# WaterMonitorV7_0.net
KiCad netlist of a schematic drawn in EAGLE
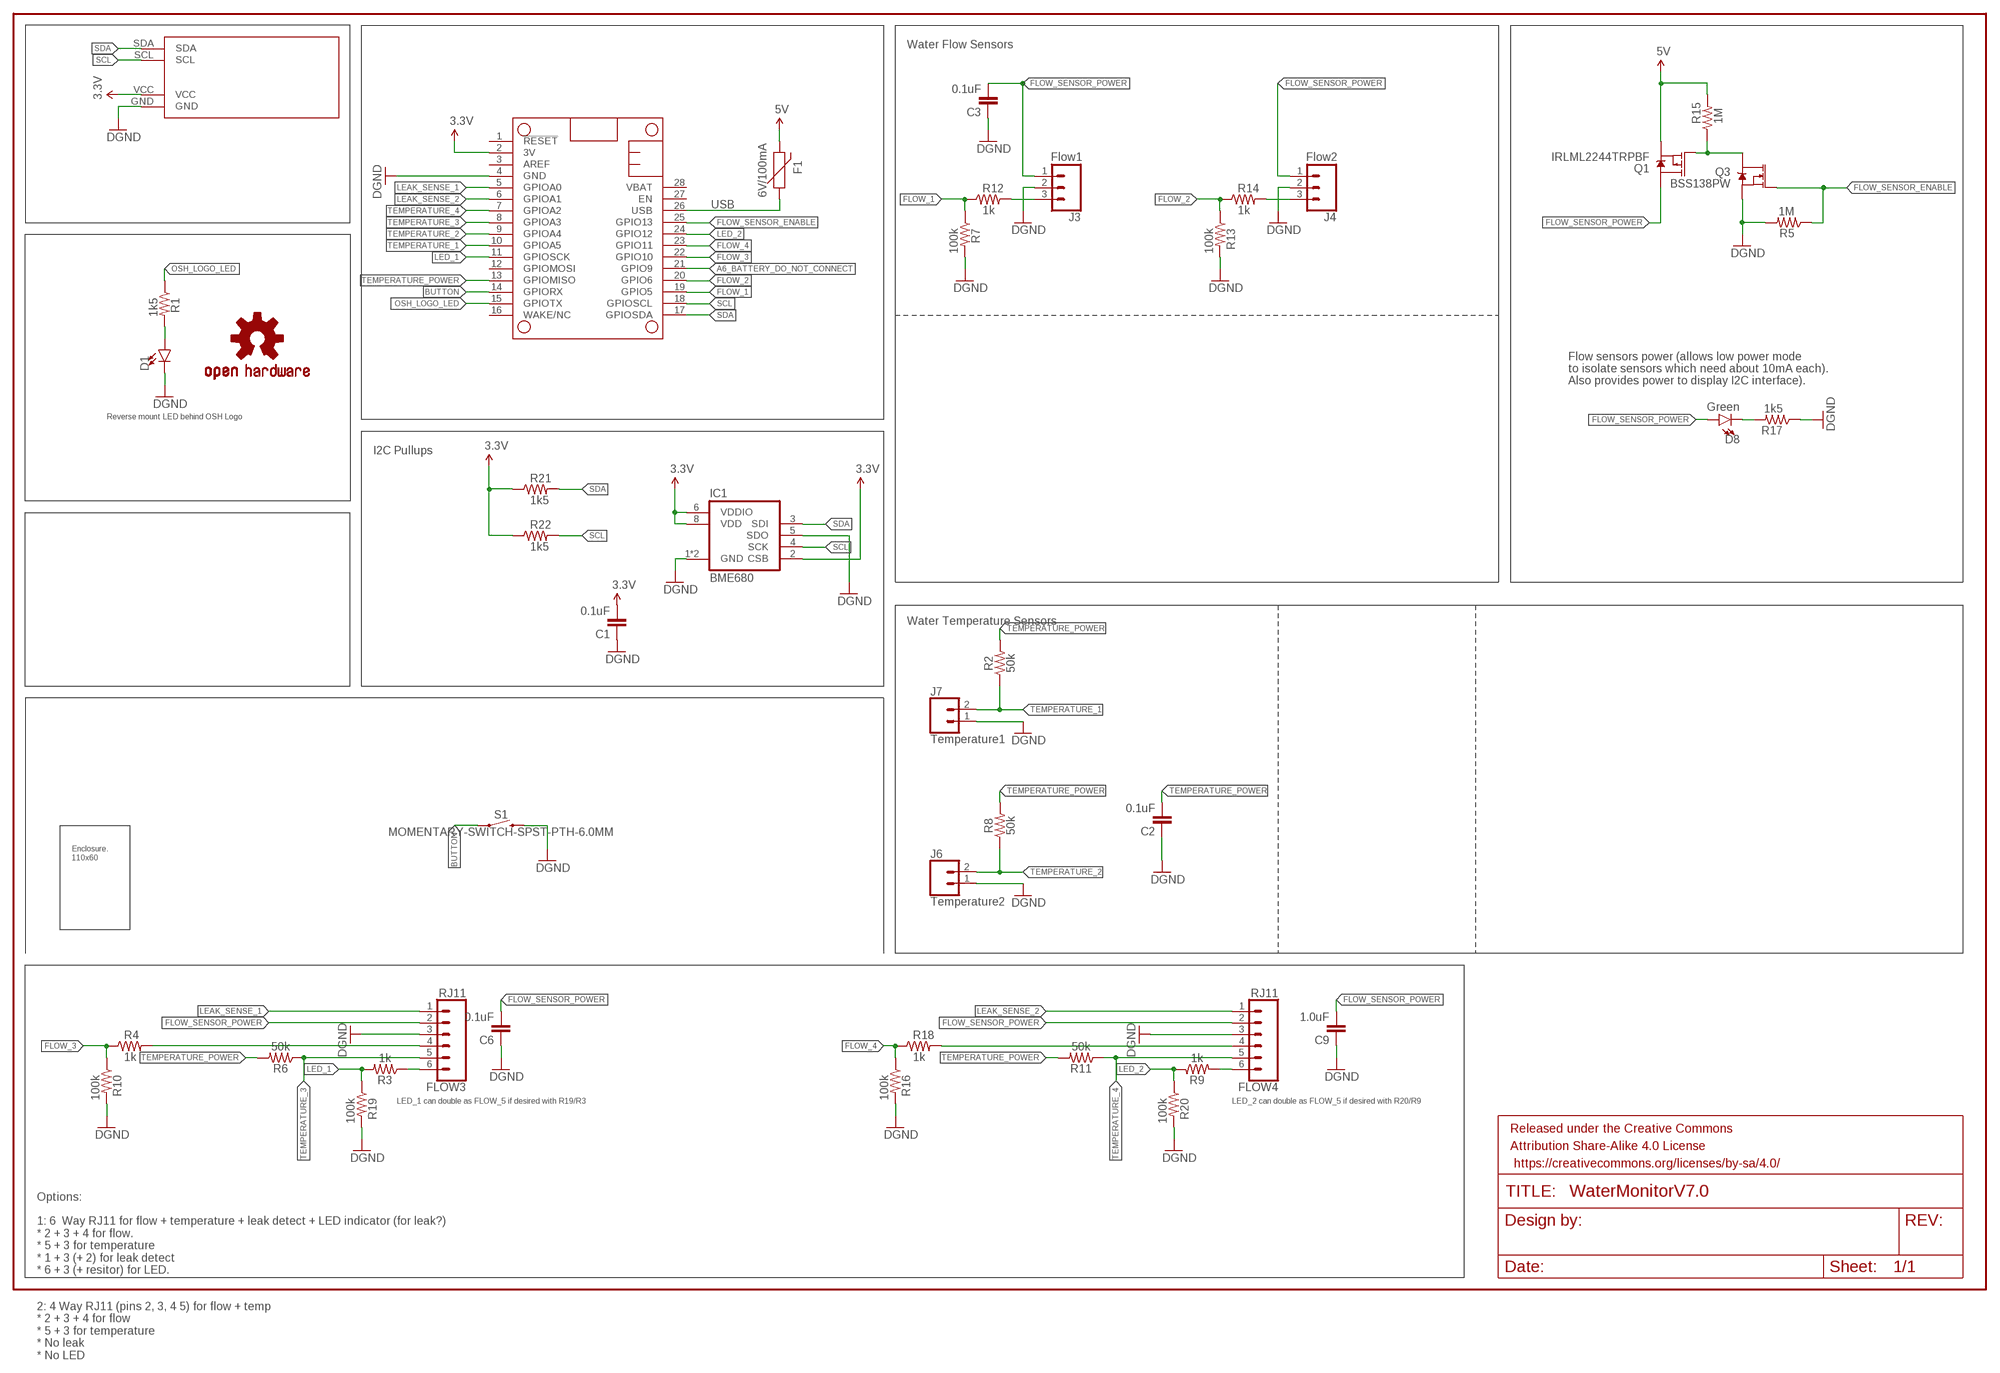
[diagram p0: schematic, sheet 1]

(export (version "E")
  (design (tool "Eeschema 10.0.6"))
  (components
    (comp (ref "C1")
      (value "0.1uF")
      (footprint "eagle-import:0805")
      (libsource (lib "eagle-import") (part "CAP0805"))
    )
    (comp (ref "C2")
      (value "0.1uF")
      (footprint "eagle-import:0805")
      (libsource (lib "eagle-import") (part "CAP0805"))
    )
    (comp (ref "C3")
      (value "0.1uF")
      (footprint "eagle-import:0805")
      (libsource (lib "eagle-import") (part "CAP0805"))
    )
    (comp (ref "C6")
      (value "0.1uF")
      (footprint "eagle-import:0805")
      (libsource (lib "eagle-import") (part "CAP0805"))
    )
    (comp (ref "C9")
      (value "1.0uF")
      (footprint "eagle-import:0805")
      (libsource (lib "eagle-import") (part "CAP0805"))
    )
    (comp (ref "D1")
      (value "LED1206-BOTTOM")
      (footprint "eagle-import:LED-1206-BOTTOM")
      (libsource (lib "eagle-import") (part "LED1206-BOTTOM"))
    )
    (comp (ref "D8")
      (value "Green")
      (footprint "eagle-import:LED-1206")
      (libsource (lib "eagle-import") (part "LED-BLUE1206"))
    )
    (comp (ref "F1")
      (value "6V/100mA")
      (footprint "eagle-import:1206")
      (libsource (lib "eagle-import") (part "PPTC_HALF-AMP"))
    )
    (comp (ref "FLOW3")
      (value "RJ11")
      (footprint "eagle-import:RJ11-6")
      (libsource (lib "eagle-import") (part "RJ11-6"))
    )
    (comp (ref "FLOW4")
      (value "RJ11")
      (footprint "eagle-import:RJ11-6")
      (libsource (lib "eagle-import") (part "RJ11-6"))
    )
    (comp (ref "FRAME2")
      (value "FRAME-LEDGER")
      (footprint "eagle-import:CREATIVE_COMMONS")
      (libsource (lib "eagle-import") (part "FRAME-LEDGER"))
    )
    (comp (ref "IC1")
      (value "BME680")
      (footprint "eagle-import:BME680")
      (libsource (lib "eagle-import") (part "BME680"))
    )
    (comp (ref "J3")
      (value "Flow1")
      (footprint "eagle-import:JST-HX-3-PTH-VERT")
      (libsource (lib "eagle-import") (part "CONN_03JST-HX-PTH-VERT"))
    )
    (comp (ref "J4")
      (value "Flow2")
      (footprint "eagle-import:JST-HX-3-PTH-VERT")
      (libsource (lib "eagle-import") (part "CONN_03JST-HX-PTH-VERT"))
    )
    (comp (ref "J6")
      (value "Temperature2")
      (footprint "eagle-import:MOLEX-1X2")
      (libsource (lib "eagle-import") (part "CONN_02POLAR"))
    )
    (comp (ref "J7")
      (value "Temperature1")
      (footprint "eagle-import:MOLEX-1X2")
      (libsource (lib "eagle-import") (part "CONN_02POLAR"))
    )
    (comp (ref "LOGO1")
      (value "OSHW-LOGOM")
      (footprint "eagle-import:OSHW-LOGO-M")
      (libsource (lib "eagle-import") (part "OSHW-LOGOM"))
    )
    (comp (ref "MS1")
      (value "FEATHERWINGSIMPLE")
      (footprint "eagle-import:FEATHERWING_BREAKOUT_SIMPLE")
      (libsource (lib "eagle-import") (part "FEATHERWINGSIMPLE"))
    )
    (comp (ref "Q1")
      (value "IRLML2244TRPBF")
      (footprint "eagle-import:SOT23-3")
      (libsource (lib "eagle-import") (part "MOSFET_PCH-IRLML2244"))
    )
    (comp (ref "Q3")
      (value "BSS138PW")
      (footprint "eagle-import:SOT23-3")
      (libsource (lib "eagle-import") (part "MOSFET-NCH-BSS138"))
    )
    (comp (ref "R1")
      (value "1k5")
      (footprint "eagle-import:0805")
      (libsource (lib "eagle-import") (part "RESISTOR0805"))
    )
    (comp (ref "R2")
      (value "50k")
      (footprint "eagle-import:0805")
      (libsource (lib "eagle-import") (part "RESISTOR0805"))
    )
    (comp (ref "R3")
      (value "1k")
      (footprint "eagle-import:0805")
      (libsource (lib "eagle-import") (part "RESISTOR0805"))
    )
    (comp (ref "R4")
      (value "1k")
      (footprint "eagle-import:0805")
      (libsource (lib "eagle-import") (part "RESISTOR0805"))
    )
    (comp (ref "R5")
      (value "1M")
      (footprint "eagle-import:0805")
      (libsource (lib "eagle-import") (part "RESISTOR0805"))
    )
    (comp (ref "R6")
      (value "50k")
      (footprint "eagle-import:0805")
      (libsource (lib "eagle-import") (part "RESISTOR0805"))
    )
    (comp (ref "R7")
      (value "100k")
      (footprint "eagle-import:0805")
      (libsource (lib "eagle-import") (part "RESISTOR0805"))
    )
    (comp (ref "R8")
      (value "50k")
      (footprint "eagle-import:0805")
      (libsource (lib "eagle-import") (part "RESISTOR0805"))
    )
    (comp (ref "R9")
      (value "1k")
      (footprint "eagle-import:0805")
      (libsource (lib "eagle-import") (part "RESISTOR0805"))
    )
    (comp (ref "R10")
      (value "100k")
      (footprint "eagle-import:0805")
      (libsource (lib "eagle-import") (part "RESISTOR0805"))
    )
    (comp (ref "R11")
      (value "50k")
      (footprint "eagle-import:0805")
      (libsource (lib "eagle-import") (part "RESISTOR0805"))
    )
    (comp (ref "R12")
      (value "1k")
      (footprint "eagle-import:0805")
      (libsource (lib "eagle-import") (part "RESISTOR0805"))
    )
    (comp (ref "R13")
      (value "100k")
      (footprint "eagle-import:0805")
      (libsource (lib "eagle-import") (part "RESISTOR0805"))
    )
    (comp (ref "R14")
      (value "1k")
      (footprint "eagle-import:0805")
      (libsource (lib "eagle-import") (part "RESISTOR0805"))
    )
    (comp (ref "R15")
      (value "1M")
      (footprint "eagle-import:0805")
      (libsource (lib "eagle-import") (part "RESISTOR0805"))
    )
    (comp (ref "R16")
      (value "100k")
      (footprint "eagle-import:0805")
      (libsource (lib "eagle-import") (part "RESISTOR0805"))
    )
    (comp (ref "R17")
      (value "1k5")
      (footprint "eagle-import:0805")
      (libsource (lib "eagle-import") (part "RESISTOR0805"))
    )
    (comp (ref "R18")
      (value "1k")
      (footprint "eagle-import:0805")
      (libsource (lib "eagle-import") (part "RESISTOR0805"))
    )
    (comp (ref "R19")
      (value "100k")
      (footprint "eagle-import:0805")
      (libsource (lib "eagle-import") (part "RESISTOR0805"))
    )
    (comp (ref "R20")
      (value "100k")
      (footprint "eagle-import:0805")
      (libsource (lib "eagle-import") (part "RESISTOR0805"))
    )
    (comp (ref "R21")
      (value "1k5")
      (footprint "eagle-import:0805")
      (libsource (lib "eagle-import") (part "RESISTOR0805"))
    )
    (comp (ref "R22")
      (value "1k5")
      (footprint "eagle-import:0805")
      (libsource (lib "eagle-import") (part "RESISTOR0805"))
    )
    (comp (ref "S1")
      (value "MOMENTARY-SWITCH-SPST-PTH-6.0MM")
      (footprint "eagle-import:TACTILE_SWITCH_PTH_6.0MM")
      (libsource (lib "eagle-import") (part "MOMENTARY-SWITCH-SPST-PTH-6.0MM"))
    )
    (comp (ref "U$1")
      (value "CAMDENBOSS-ENCLOSURE-110X60BOTH-EXTENDED-WIDE")
      (footprint "eagle-import:CAMDENBOSS_ENCLOSURE_110X60_WIDE_EXTENDED")
      (libsource (lib "eagle-import") (part "CAMDENBOSS-ENCLOSURE-110X60BOTH-EXTENDED-WIDE"))
    )
    (comp (ref "U$2")
      (value "DISPLAY0.96_INCH_DISPLAY")
      (footprint "eagle-import:I2C_DISPLAY_0.96_INCH")
      (libsource (lib "eagle-import") (part "DISPLAY0.96_INCH_DISPLAY"))
    )
  )
  (nets
    (net (code "1") (name "/USB") (class "Default")
      (node (ref "F1") (pin "1") (pinfunction "1_1") (pintype "bidirectional"))
      (node (ref "MS1") (pin "26") (pinfunction "USB_26") (pintype "power_in"))
    )
    (net (code "2") (name "/VBAT") (class "Default")
      (node (ref "MS1") (pin "28") (pinfunction "VBAT_28") (pintype "power_in"))
    )
    (net (code "3") (name "3.3V") (class "Default")
      (node (ref "C1") (pin "2") (pinfunction "2_2") (pintype "passive"))
      (node (ref "IC1") (pin "2") (pinfunction "CSB_2") (pintype "input"))
      (node (ref "IC1") (pin "6") (pinfunction "VDDIO_6") (pintype "power_in"))
      (node (ref "IC1") (pin "8") (pinfunction "VDD_8") (pintype "power_in"))
      (node (ref "MS1") (pin "2") (pinfunction "3V_2") (pintype "power_in"))
      (node (ref "R21") (pin "1") (pinfunction "1_1") (pintype "passive"))
      (node (ref "R22") (pin "1") (pinfunction "1_1") (pintype "passive"))
      (node (ref "U$2") (pin "VCC") (pinfunction "VCC_VCC") (pintype "power_in"))
    )
    (net (code "4") (name "5V") (class "Default")
      (node (ref "F1") (pin "2") (pinfunction "2_2") (pintype "bidirectional"))
      (node (ref "Q1") (pin "2") (pinfunction "S_2") (pintype "bidirectional"))
      (node (ref "R15") (pin "2") (pinfunction "2_2") (pintype "passive"))
    )
    (net (code "5") (name "A6_BATTERY_DO_NOT_CONNECT") (class "Default")
      (node (ref "MS1") (pin "21") (pinfunction "GPIO9_21") (pintype "bidirectional"))
    )
    (net (code "6") (name "BUTTON") (class "Default")
      (node (ref "MS1") (pin "14") (pinfunction "GPIORX_14") (pintype "bidirectional"))
      (node (ref "S1") (pin "1") (pinfunction "1_1") (pintype "passive"))
    )
    (net (code "7") (name "DGND") (class "Default")
      (node (ref "C1") (pin "1") (pinfunction "1_1") (pintype "passive"))
      (node (ref "C2") (pin "1") (pinfunction "1_1") (pintype "passive"))
      (node (ref "C3") (pin "1") (pinfunction "1_1") (pintype "passive"))
      (node (ref "C6") (pin "1") (pinfunction "1_1") (pintype "passive"))
      (node (ref "C9") (pin "1") (pinfunction "1_1") (pintype "passive"))
      (node (ref "D1") (pin "C") (pinfunction "C_C") (pintype "passive"))
      (node (ref "FLOW3") (pin "3") (pinfunction "3_3") (pintype "passive"))
      (node (ref "FLOW4") (pin "3") (pinfunction "3_3") (pintype "passive"))
      (node (ref "IC1") (pin "1") (pinfunction "GND_1") (pintype "power_in"))
      (node (ref "IC1") (pin "5") (pinfunction "SDO_5") (pintype "output"))
      (node (ref "IC1") (pin "7") (pinfunction "GND_7") (pintype "power_in"))
      (node (ref "J3") (pin "2") (pinfunction "2_2") (pintype "passive"))
      (node (ref "J4") (pin "2") (pinfunction "2_2") (pintype "passive"))
      (node (ref "J6") (pin "1") (pinfunction "1_1") (pintype "passive"))
      (node (ref "J7") (pin "1") (pinfunction "1_1") (pintype "passive"))
      (node (ref "MS1") (pin "4") (pinfunction "GND_4") (pintype "power_in"))
      (node (ref "Q3") (pin "2") (pinfunction "S_2") (pintype "bidirectional"))
      (node (ref "R10") (pin "2") (pinfunction "2_2") (pintype "passive"))
      (node (ref "R13") (pin "2") (pinfunction "2_2") (pintype "passive"))
      (node (ref "R16") (pin "2") (pinfunction "2_2") (pintype "passive"))
      (node (ref "R17") (pin "1") (pinfunction "1_1") (pintype "passive"))
      (node (ref "R19") (pin "2") (pinfunction "2_2") (pintype "passive"))
      (node (ref "R20") (pin "2") (pinfunction "2_2") (pintype "passive"))
      (node (ref "R5") (pin "2") (pinfunction "2_2") (pintype "passive"))
      (node (ref "R7") (pin "2") (pinfunction "2_2") (pintype "passive"))
      (node (ref "S1") (pin "3") (pinfunction "2_3") (pintype "passive"))
      (node (ref "U$2") (pin "GND") (pinfunction "GND_GND") (pintype "power_in"))
    )
    (net (code "8") (name "FLOW_1") (class "Default")
      (node (ref "MS1") (pin "19") (pinfunction "GPIO5_19") (pintype "bidirectional"))
      (node (ref "R12") (pin "1") (pinfunction "1_1") (pintype "passive"))
      (node (ref "R7") (pin "1") (pinfunction "1_1") (pintype "passive"))
    )
    (net (code "9") (name "FLOW_2") (class "Default")
      (node (ref "MS1") (pin "20") (pinfunction "GPIO6_20") (pintype "bidirectional"))
      (node (ref "R13") (pin "1") (pinfunction "1_1") (pintype "passive"))
      (node (ref "R14") (pin "1") (pinfunction "1_1") (pintype "passive"))
    )
    (net (code "10") (name "FLOW_3") (class "Default")
      (node (ref "MS1") (pin "22") (pinfunction "GPIO10_22") (pintype "bidirectional"))
      (node (ref "R10") (pin "1") (pinfunction "1_1") (pintype "passive"))
      (node (ref "R4") (pin "1") (pinfunction "1_1") (pintype "passive"))
    )
    (net (code "11") (name "FLOW_4") (class "Default")
      (node (ref "MS1") (pin "23") (pinfunction "GPIO11_23") (pintype "bidirectional"))
      (node (ref "R16") (pin "1") (pinfunction "1_1") (pintype "passive"))
      (node (ref "R18") (pin "1") (pinfunction "1_1") (pintype "passive"))
    )
    (net (code "12") (name "FLOW_SENSOR_ENABLE") (class "Default")
      (node (ref "MS1") (pin "25") (pinfunction "GPIO13_25") (pintype "bidirectional"))
      (node (ref "Q3") (pin "1") (pinfunction "G_1") (pintype "bidirectional"))
      (node (ref "R5") (pin "1") (pinfunction "1_1") (pintype "passive"))
    )
    (net (code "13") (name "FLOW_SENSOR_POWER") (class "Default")
      (node (ref "C3") (pin "2") (pinfunction "2_2") (pintype "passive"))
      (node (ref "C6") (pin "2") (pinfunction "2_2") (pintype "passive"))
      (node (ref "C9") (pin "2") (pinfunction "2_2") (pintype "passive"))
      (node (ref "D8") (pin "A") (pinfunction "A_A") (pintype "passive"))
      (node (ref "FLOW3") (pin "2") (pinfunction "2_2") (pintype "passive"))
      (node (ref "FLOW4") (pin "2") (pinfunction "2_2") (pintype "passive"))
      (node (ref "J3") (pin "1") (pinfunction "1_1") (pintype "passive"))
      (node (ref "J4") (pin "1") (pinfunction "1_1") (pintype "passive"))
      (node (ref "Q1") (pin "3") (pinfunction "D_3") (pintype "bidirectional"))
    )
    (net (code "14") (name "LEAK_SENSE_1") (class "Default")
      (node (ref "FLOW3") (pin "1") (pinfunction "1_1") (pintype "passive"))
      (node (ref "MS1") (pin "5") (pinfunction "GPIOA0_5") (pintype "bidirectional"))
    )
    (net (code "15") (name "LEAK_SENSE_2") (class "Default")
      (node (ref "FLOW4") (pin "1") (pinfunction "1_1") (pintype "passive"))
      (node (ref "MS1") (pin "6") (pinfunction "GPIOA1_6") (pintype "bidirectional"))
    )
    (net (code "16") (name "LED_1") (class "Default")
      (node (ref "MS1") (pin "11") (pinfunction "GPIOSCK_11") (pintype "bidirectional"))
      (node (ref "R19") (pin "1") (pinfunction "1_1") (pintype "passive"))
      (node (ref "R3") (pin "2") (pinfunction "2_2") (pintype "passive"))
    )
    (net (code "17") (name "LED_2") (class "Default")
      (node (ref "MS1") (pin "24") (pinfunction "GPIO12_24") (pintype "bidirectional"))
      (node (ref "R20") (pin "1") (pinfunction "1_1") (pintype "passive"))
      (node (ref "R9") (pin "1") (pinfunction "1_1") (pintype "passive"))
    )
    (net (code "18") (name "Net-(D1-PadA)") (class "Default")
      (node (ref "D1") (pin "A") (pinfunction "A_A") (pintype "passive"))
      (node (ref "R1") (pin "2") (pinfunction "2_2") (pintype "passive"))
    )
    (net (code "19") (name "Net-(D8-PadC)") (class "Default")
      (node (ref "D8") (pin "C") (pinfunction "C_C") (pintype "passive"))
      (node (ref "R17") (pin "2") (pinfunction "2_2") (pintype "passive"))
    )
    (net (code "20") (name "Net-(FLOW3-Pad4)") (class "Default")
      (node (ref "FLOW3") (pin "4") (pinfunction "4_4") (pintype "passive"))
      (node (ref "R4") (pin "2") (pinfunction "2_2") (pintype "passive"))
    )
    (net (code "21") (name "Net-(FLOW3-Pad6)") (class "Default")
      (node (ref "FLOW3") (pin "6") (pinfunction "6_6") (pintype "passive"))
      (node (ref "R3") (pin "1") (pinfunction "1_1") (pintype "passive"))
    )
    (net (code "22") (name "Net-(FLOW4-Pad4)") (class "Default")
      (node (ref "FLOW4") (pin "4") (pinfunction "4_4") (pintype "passive"))
      (node (ref "R18") (pin "2") (pinfunction "2_2") (pintype "passive"))
    )
    (net (code "23") (name "Net-(FLOW4-Pad6)") (class "Default")
      (node (ref "FLOW4") (pin "6") (pinfunction "6_6") (pintype "passive"))
      (node (ref "R9") (pin "2") (pinfunction "2_2") (pintype "passive"))
    )
    (net (code "24") (name "Net-(J3-Pad3)") (class "Default")
      (node (ref "J3") (pin "3") (pinfunction "3_3") (pintype "passive"))
      (node (ref "R12") (pin "2") (pinfunction "2_2") (pintype "passive"))
    )
    (net (code "25") (name "Net-(J4-Pad3)") (class "Default")
      (node (ref "J4") (pin "3") (pinfunction "3_3") (pintype "passive"))
      (node (ref "R14") (pin "2") (pinfunction "2_2") (pintype "passive"))
    )
    (net (code "26") (name "Net-(Q1-G)") (class "Default")
      (node (ref "Q1") (pin "1") (pinfunction "G_1") (pintype "bidirectional"))
      (node (ref "Q3") (pin "3") (pinfunction "D_3") (pintype "bidirectional"))
      (node (ref "R15") (pin "1") (pinfunction "1_1") (pintype "passive"))
    )
    (net (code "27") (name "OSH_LOGO_LED") (class "Default")
      (node (ref "MS1") (pin "15") (pinfunction "GPIOTX_15") (pintype "bidirectional"))
      (node (ref "R1") (pin "1") (pinfunction "1_1") (pintype "passive"))
    )
    (net (code "28") (name "SCL") (class "Default")
      (node (ref "IC1") (pin "4") (pinfunction "SCK_4") (pintype "input"))
      (node (ref "MS1") (pin "18") (pinfunction "GPIOSCL_18") (pintype "bidirectional"))
      (node (ref "R22") (pin "2") (pinfunction "2_2") (pintype "passive"))
      (node (ref "U$2") (pin "SCL") (pinfunction "SCL_SCL") (pintype "bidirectional"))
    )
    (net (code "29") (name "SDA") (class "Default")
      (node (ref "IC1") (pin "3") (pinfunction "SDI_3") (pintype "input"))
      (node (ref "MS1") (pin "17") (pinfunction "GPIOSDA_17") (pintype "bidirectional"))
      (node (ref "R21") (pin "2") (pinfunction "2_2") (pintype "passive"))
      (node (ref "U$2") (pin "SDA") (pinfunction "SDA_SDA") (pintype "bidirectional"))
    )
    (net (code "30") (name "TEMPERATURE_1") (class "Default")
      (node (ref "J7") (pin "2") (pinfunction "2_2") (pintype "passive"))
      (node (ref "MS1") (pin "10") (pinfunction "GPIOA5_10") (pintype "bidirectional"))
      (node (ref "R2") (pin "1") (pinfunction "1_1") (pintype "passive"))
    )
    (net (code "31") (name "TEMPERATURE_2") (class "Default")
      (node (ref "J6") (pin "2") (pinfunction "2_2") (pintype "passive"))
      (node (ref "MS1") (pin "9") (pinfunction "GPIOA4_9") (pintype "bidirectional"))
      (node (ref "R8") (pin "1") (pinfunction "1_1") (pintype "passive"))
    )
    (net (code "32") (name "TEMPERATURE_3") (class "Default")
      (node (ref "FLOW3") (pin "5") (pinfunction "5_5") (pintype "passive"))
      (node (ref "MS1") (pin "8") (pinfunction "GPIOA3_8") (pintype "bidirectional"))
      (node (ref "R6") (pin "1") (pinfunction "1_1") (pintype "passive"))
    )
    (net (code "33") (name "TEMPERATURE_4") (class "Default")
      (node (ref "FLOW4") (pin "5") (pinfunction "5_5") (pintype "passive"))
      (node (ref "MS1") (pin "7") (pinfunction "GPIOA2_7") (pintype "bidirectional"))
      (node (ref "R11") (pin "1") (pinfunction "1_1") (pintype "passive"))
    )
    (net (code "34") (name "TEMPERATURE_POWER") (class "Default")
      (node (ref "C2") (pin "2") (pinfunction "2_2") (pintype "passive"))
      (node (ref "MS1") (pin "13") (pinfunction "GPIOMISO_13") (pintype "bidirectional"))
      (node (ref "R11") (pin "2") (pinfunction "2_2") (pintype "passive"))
      (node (ref "R2") (pin "2") (pinfunction "2_2") (pintype "passive"))
      (node (ref "R6") (pin "2") (pinfunction "2_2") (pintype "passive"))
      (node (ref "R8") (pin "2") (pinfunction "2_2") (pintype "passive"))
    )
    (net (code "35") (name "unconnected-(MS1-AREF-Pad3)") (class "Default")
      (node (ref "MS1") (pin "3") (pinfunction "AREF_3") (pintype "passive"))
    )
    (net (code "36") (name "unconnected-(MS1-EN-Pad27)") (class "Default")
      (node (ref "MS1") (pin "27") (pinfunction "EN_27") (pintype "passive"))
    )
    (net (code "37") (name "unconnected-(MS1-GPIOMOSI-Pad12)") (class "Default")
      (node (ref "MS1") (pin "12") (pinfunction "GPIOMOSI_12") (pintype "bidirectional"))
    )
    (net (code "38") (name "unconnected-(MS1-WAKE{slash}NC-Pad16)") (class "Default")
      (node (ref "MS1") (pin "16") (pinfunction "WAKE/NC_16") (pintype "passive"))
    )
    (net (code "39") (name "unconnected-(MS1-~{RESET}-Pad1)") (class "Default")
      (node (ref "MS1") (pin "1") (pinfunction "~{RESET}_1") (pintype "input"))
    )
  )
)
